# arduino_minimal.net
KiCad netlist of a schematic drawn in EAGLE
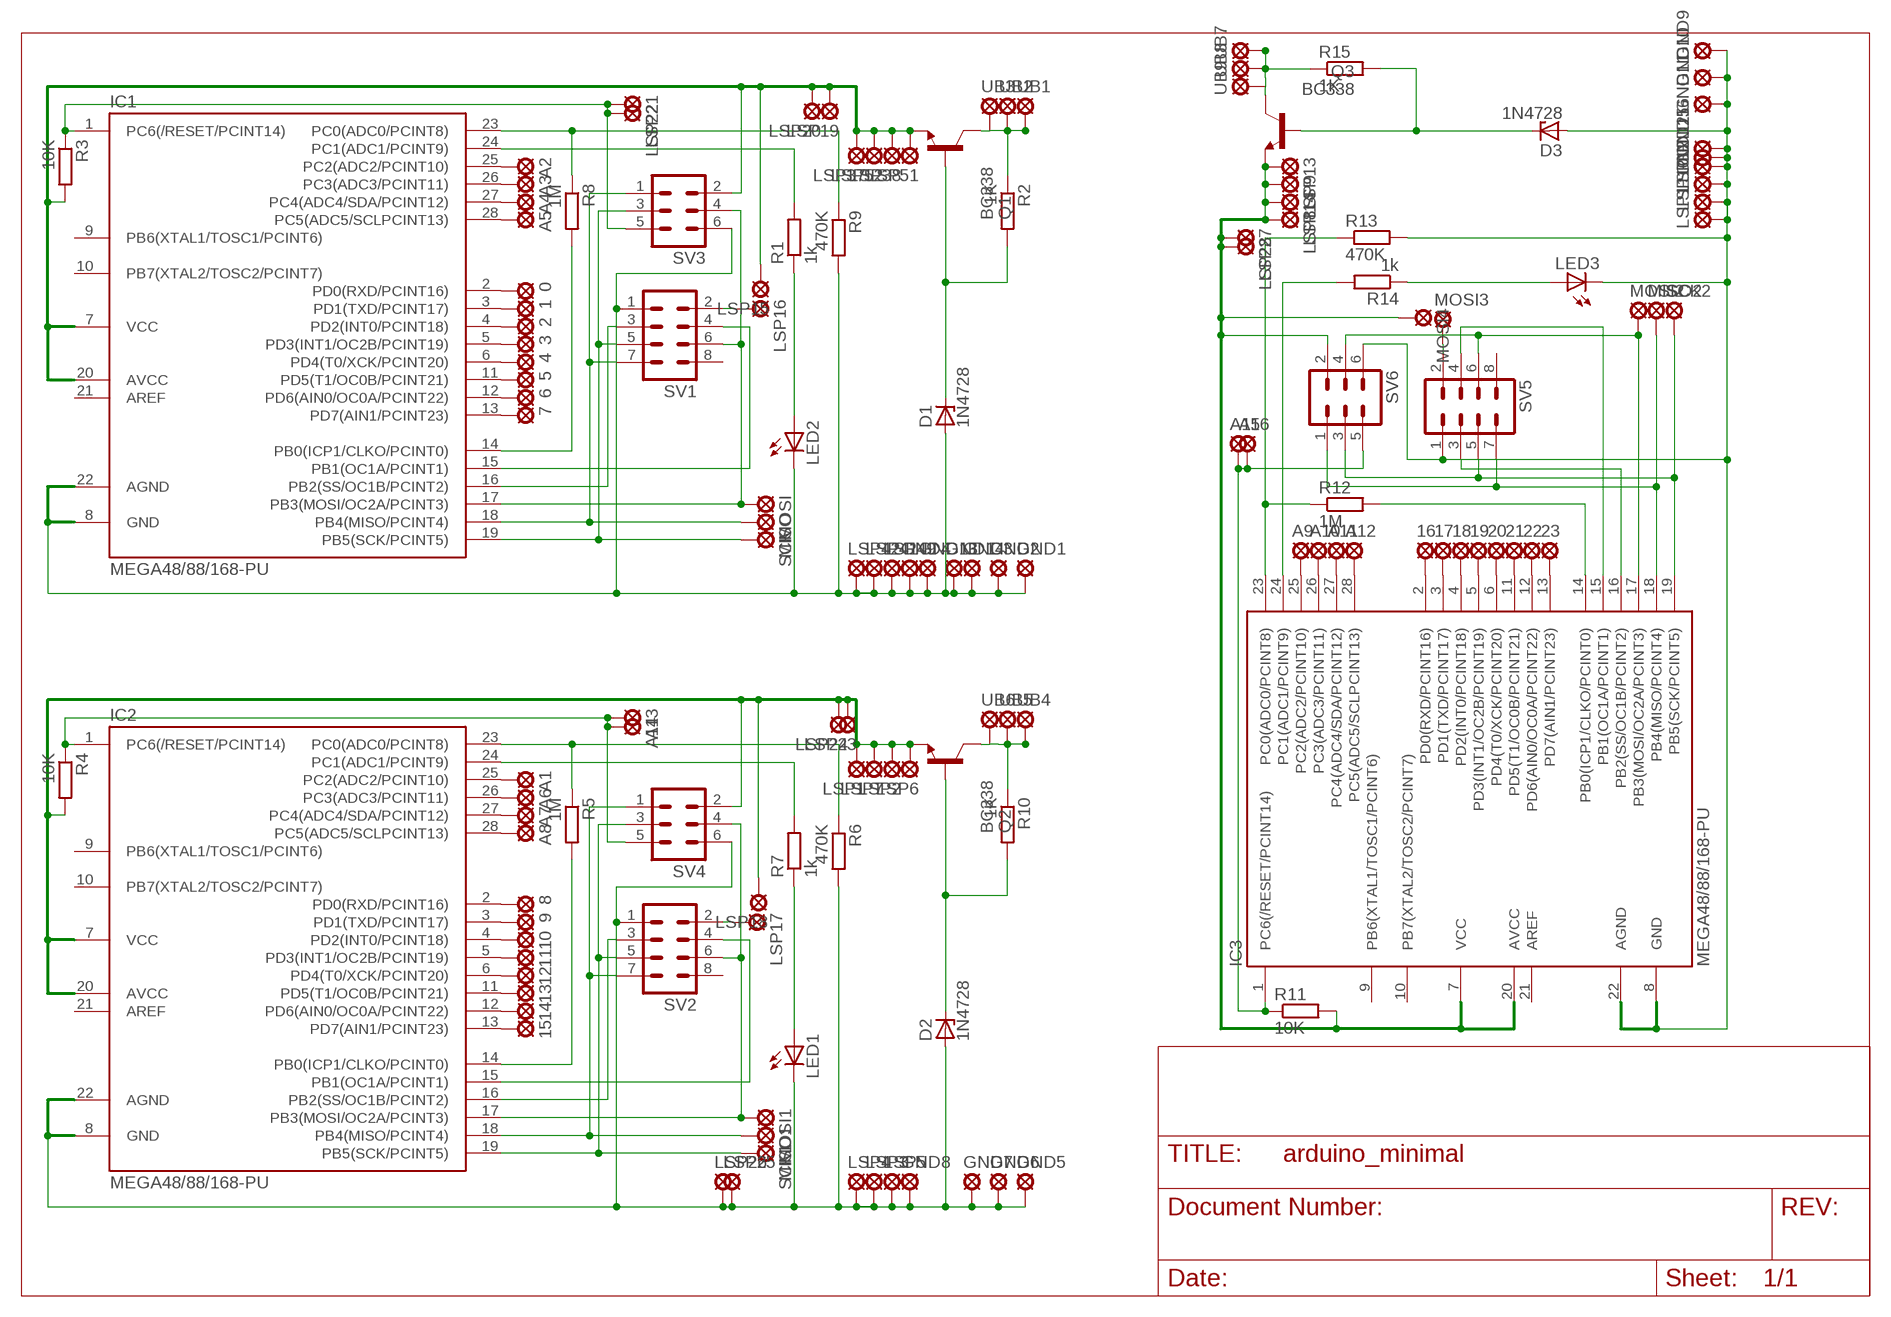
[diagram p0: schematic, sheet 1]

(export (version "E")
  (design (tool "Eeschema 10.0.6"))
  (components
    (comp (ref "0")
      (value "LSP10")
      (footprint "eagle-import:LSP10")
      (libsource (lib "eagle-import") (part "LSP10"))
    )
    (comp (ref "1")
      (value "LSP10")
      (footprint "eagle-import:LSP10")
      (libsource (lib "eagle-import") (part "LSP10"))
    )
    (comp (ref "2")
      (value "LSP10")
      (footprint "eagle-import:LSP10")
      (libsource (lib "eagle-import") (part "LSP10"))
    )
    (comp (ref "3")
      (value "LSP10")
      (footprint "eagle-import:LSP10")
      (libsource (lib "eagle-import") (part "LSP10"))
    )
    (comp (ref "4")
      (value "LSP10")
      (footprint "eagle-import:LSP10")
      (libsource (lib "eagle-import") (part "LSP10"))
    )
    (comp (ref "5")
      (value "LSP10")
      (footprint "eagle-import:LSP10")
      (libsource (lib "eagle-import") (part "LSP10"))
    )
    (comp (ref "6")
      (value "LSP10")
      (footprint "eagle-import:LSP10")
      (libsource (lib "eagle-import") (part "LSP10"))
    )
    (comp (ref "7")
      (value "LSP10")
      (footprint "eagle-import:LSP10")
      (libsource (lib "eagle-import") (part "LSP10"))
    )
    (comp (ref "8")
      (value "LSP10")
      (footprint "eagle-import:LSP10")
      (libsource (lib "eagle-import") (part "LSP10"))
    )
    (comp (ref "9")
      (value "LSP10")
      (footprint "eagle-import:LSP10")
      (libsource (lib "eagle-import") (part "LSP10"))
    )
    (comp (ref "10")
      (value "LSP10")
      (footprint "eagle-import:LSP10")
      (libsource (lib "eagle-import") (part "LSP10"))
    )
    (comp (ref "11")
      (value "LSP10")
      (footprint "eagle-import:LSP10")
      (libsource (lib "eagle-import") (part "LSP10"))
    )
    (comp (ref "12")
      (value "LSP10")
      (footprint "eagle-import:LSP10")
      (libsource (lib "eagle-import") (part "LSP10"))
    )
    (comp (ref "13")
      (value "LSP10")
      (footprint "eagle-import:LSP10")
      (libsource (lib "eagle-import") (part "LSP10"))
    )
    (comp (ref "14")
      (value "LSP10")
      (footprint "eagle-import:LSP10")
      (libsource (lib "eagle-import") (part "LSP10"))
    )
    (comp (ref "15")
      (value "LSP10")
      (footprint "eagle-import:LSP10")
      (libsource (lib "eagle-import") (part "LSP10"))
    )
    (comp (ref "16")
      (value "LSP10")
      (footprint "eagle-import:LSP10")
      (libsource (lib "eagle-import") (part "LSP10"))
    )
    (comp (ref "17")
      (value "LSP10")
      (footprint "eagle-import:LSP10")
      (libsource (lib "eagle-import") (part "LSP10"))
    )
    (comp (ref "18")
      (value "LSP10")
      (footprint "eagle-import:LSP10")
      (libsource (lib "eagle-import") (part "LSP10"))
    )
    (comp (ref "19")
      (value "LSP10")
      (footprint "eagle-import:LSP10")
      (libsource (lib "eagle-import") (part "LSP10"))
    )
    (comp (ref "20")
      (value "LSP10")
      (footprint "eagle-import:LSP10")
      (libsource (lib "eagle-import") (part "LSP10"))
    )
    (comp (ref "21")
      (value "LSP10")
      (footprint "eagle-import:LSP10")
      (libsource (lib "eagle-import") (part "LSP10"))
    )
    (comp (ref "22")
      (value "LSP10")
      (footprint "eagle-import:LSP10")
      (libsource (lib "eagle-import") (part "LSP10"))
    )
    (comp (ref "23")
      (value "LSP10")
      (footprint "eagle-import:LSP10")
      (libsource (lib "eagle-import") (part "LSP10"))
    )
    (comp (ref "A1")
      (value "LSP10")
      (footprint "eagle-import:LSP10")
      (libsource (lib "eagle-import") (part "LSP10"))
    )
    (comp (ref "A2")
      (value "LSP10")
      (footprint "eagle-import:LSP10")
      (libsource (lib "eagle-import") (part "LSP10"))
    )
    (comp (ref "A3")
      (value "LSP10")
      (footprint "eagle-import:LSP10")
      (libsource (lib "eagle-import") (part "LSP10"))
    )
    (comp (ref "A4")
      (value "LSP10")
      (footprint "eagle-import:LSP10")
      (libsource (lib "eagle-import") (part "LSP10"))
    )
    (comp (ref "A5")
      (value "LSP10")
      (footprint "eagle-import:LSP10")
      (libsource (lib "eagle-import") (part "LSP10"))
    )
    (comp (ref "A6")
      (value "LSP10")
      (footprint "eagle-import:LSP10")
      (libsource (lib "eagle-import") (part "LSP10"))
    )
    (comp (ref "A7")
      (value "LSP10")
      (footprint "eagle-import:LSP10")
      (libsource (lib "eagle-import") (part "LSP10"))
    )
    (comp (ref "A8")
      (value "LSP10")
      (footprint "eagle-import:LSP10")
      (libsource (lib "eagle-import") (part "LSP10"))
    )
    (comp (ref "A9")
      (value "LSP10")
      (footprint "eagle-import:LSP10")
      (libsource (lib "eagle-import") (part "LSP10"))
    )
    (comp (ref "A10")
      (value "LSP10")
      (footprint "eagle-import:LSP10")
      (libsource (lib "eagle-import") (part "LSP10"))
    )
    (comp (ref "A11")
      (value "LSP10")
      (footprint "eagle-import:LSP10")
      (libsource (lib "eagle-import") (part "LSP10"))
    )
    (comp (ref "A12")
      (value "LSP10")
      (footprint "eagle-import:LSP10")
      (libsource (lib "eagle-import") (part "LSP10"))
    )
    (comp (ref "A13")
      (value "LSP10")
      (footprint "eagle-import:LSP10")
      (libsource (lib "eagle-import") (part "LSP10"))
    )
    (comp (ref "A14")
      (value "LSP10")
      (footprint "eagle-import:LSP10")
      (libsource (lib "eagle-import") (part "LSP10"))
    )
    (comp (ref "A15")
      (value "LSP10")
      (footprint "eagle-import:LSP10")
      (libsource (lib "eagle-import") (part "LSP10"))
    )
    (comp (ref "A16")
      (value "LSP10")
      (footprint "eagle-import:LSP10")
      (libsource (lib "eagle-import") (part "LSP10"))
    )
    (comp (ref "D1")
      (value "1N4728")
      (footprint "eagle-import:DO41Z10")
      (libsource (lib "eagle-import") (part "1N4728"))
    )
    (comp (ref "D2")
      (value "1N4728")
      (footprint "eagle-import:DO41Z10")
      (libsource (lib "eagle-import") (part "1N4728"))
    )
    (comp (ref "D3")
      (value "1N4728")
      (footprint "eagle-import:DO41Z10")
      (libsource (lib "eagle-import") (part "1N4728"))
    )
    (comp (ref "GND1")
      (value "LSP10")
      (footprint "eagle-import:LSP10")
      (libsource (lib "eagle-import") (part "LSP10"))
    )
    (comp (ref "GND2")
      (value "LSP10")
      (footprint "eagle-import:LSP10")
      (libsource (lib "eagle-import") (part "LSP10"))
    )
    (comp (ref "GND3")
      (value "LSP10")
      (footprint "eagle-import:LSP10")
      (libsource (lib "eagle-import") (part "LSP10"))
    )
    (comp (ref "GND4")
      (value "LSP10")
      (footprint "eagle-import:LSP10")
      (libsource (lib "eagle-import") (part "LSP10"))
    )
    (comp (ref "GND5")
      (value "LSP10")
      (footprint "eagle-import:LSP10")
      (libsource (lib "eagle-import") (part "LSP10"))
    )
    (comp (ref "GND6")
      (value "LSP10")
      (footprint "eagle-import:LSP10")
      (libsource (lib "eagle-import") (part "LSP10"))
    )
    (comp (ref "GND7")
      (value "LSP10")
      (footprint "eagle-import:LSP10")
      (libsource (lib "eagle-import") (part "LSP10"))
    )
    (comp (ref "GND8")
      (value "LSP10")
      (footprint "eagle-import:LSP10")
      (libsource (lib "eagle-import") (part "LSP10"))
    )
    (comp (ref "GND9")
      (value "LSP10")
      (footprint "eagle-import:LSP10")
      (libsource (lib "eagle-import") (part "LSP10"))
    )
    (comp (ref "GND10")
      (value "LSP10")
      (footprint "eagle-import:LSP10")
      (libsource (lib "eagle-import") (part "LSP10"))
    )
    (comp (ref "GND11")
      (value "LSP10")
      (footprint "eagle-import:LSP10")
      (libsource (lib "eagle-import") (part "LSP10"))
    )
    (comp (ref "GND12")
      (value "LSP10")
      (footprint "eagle-import:LSP10")
      (libsource (lib "eagle-import") (part "LSP10"))
    )
    (comp (ref "GND13")
      (value "LSP10")
      (footprint "eagle-import:LSP10")
      (libsource (lib "eagle-import") (part "LSP10"))
    )
    (comp (ref "GND14")
      (value "LSP10")
      (footprint "eagle-import:LSP10")
      (libsource (lib "eagle-import") (part "LSP10"))
    )
    (comp (ref "GND15")
      (value "LSP10")
      (footprint "eagle-import:LSP10")
      (libsource (lib "eagle-import") (part "LSP10"))
    )
    (comp (ref "GND16")
      (value "LSP10")
      (footprint "eagle-import:LSP10")
      (libsource (lib "eagle-import") (part "LSP10"))
    )
    (comp (ref "IC1")
      (value "MEGA48/88/168-PU")
      (footprint "eagle-import:DIL28-3")
      (libsource (lib "eagle-import") (part "MEGA48/88/168-PU"))
    )
    (comp (ref "IC2")
      (value "MEGA48/88/168-PU")
      (footprint "eagle-import:DIL28-3")
      (libsource (lib "eagle-import") (part "MEGA48/88/168-PU"))
    )
    (comp (ref "IC3")
      (value "MEGA48/88/168-PU")
      (footprint "eagle-import:DIL28-3")
      (libsource (lib "eagle-import") (part "MEGA48/88/168-PU"))
    )
    (comp (ref "LED1")
      (value "LED3MM")
      (footprint "eagle-import:LED3MM")
      (libsource (lib "eagle-import") (part "LED3MM"))
    )
    (comp (ref "LED2")
      (value "LED3MM")
      (footprint "eagle-import:LED3MM")
      (libsource (lib "eagle-import") (part "LED3MM"))
    )
    (comp (ref "LED3")
      (value "LED3MM")
      (footprint "eagle-import:LED3MM")
      (libsource (lib "eagle-import") (part "LED3MM"))
    )
    (comp (ref "LSP1")
      (value "LSP10")
      (footprint "eagle-import:LSP10")
      (libsource (lib "eagle-import") (part "LSP10"))
    )
    (comp (ref "LSP2")
      (value "LSP10")
      (footprint "eagle-import:LSP10")
      (libsource (lib "eagle-import") (part "LSP10"))
    )
    (comp (ref "LSP3")
      (value "LSP10")
      (footprint "eagle-import:LSP10")
      (libsource (lib "eagle-import") (part "LSP10"))
    )
    (comp (ref "LSP4")
      (value "LSP10")
      (footprint "eagle-import:LSP10")
      (libsource (lib "eagle-import") (part "LSP10"))
    )
    (comp (ref "LSP5")
      (value "LSP10")
      (footprint "eagle-import:LSP10")
      (libsource (lib "eagle-import") (part "LSP10"))
    )
    (comp (ref "LSP6")
      (value "LSP10")
      (footprint "eagle-import:LSP10")
      (libsource (lib "eagle-import") (part "LSP10"))
    )
    (comp (ref "LSP7")
      (value "LSP10")
      (footprint "eagle-import:LSP10")
      (libsource (lib "eagle-import") (part "LSP10"))
    )
    (comp (ref "LSP8")
      (value "LSP10")
      (footprint "eagle-import:LSP10")
      (libsource (lib "eagle-import") (part "LSP10"))
    )
    (comp (ref "LSP9")
      (value "LSP10")
      (footprint "eagle-import:LSP10")
      (libsource (lib "eagle-import") (part "LSP10"))
    )
    (comp (ref "LSP10")
      (value "LSP10")
      (footprint "eagle-import:LSP10")
      (libsource (lib "eagle-import") (part "LSP10"))
    )
    (comp (ref "LSP11")
      (value "LSP10")
      (footprint "eagle-import:LSP10")
      (libsource (lib "eagle-import") (part "LSP10"))
    )
    (comp (ref "LSP12")
      (value "LSP10")
      (footprint "eagle-import:LSP10")
      (libsource (lib "eagle-import") (part "LSP10"))
    )
    (comp (ref "LSP13")
      (value "LSP10")
      (footprint "eagle-import:LSP10")
      (libsource (lib "eagle-import") (part "LSP10"))
    )
    (comp (ref "LSP14")
      (value "LSP10")
      (footprint "eagle-import:LSP10")
      (libsource (lib "eagle-import") (part "LSP10"))
    )
    (comp (ref "LSP15")
      (value "LSP10")
      (footprint "eagle-import:LSP10")
      (libsource (lib "eagle-import") (part "LSP10"))
    )
    (comp (ref "LSP16")
      (value "LSP10")
      (footprint "eagle-import:LSP10")
      (libsource (lib "eagle-import") (part "LSP10"))
    )
    (comp (ref "LSP17")
      (value "LSP10")
      (footprint "eagle-import:LSP10")
      (libsource (lib "eagle-import") (part "LSP10"))
    )
    (comp (ref "LSP18")
      (value "LSP10")
      (footprint "eagle-import:LSP10")
      (libsource (lib "eagle-import") (part "LSP10"))
    )
    (comp (ref "LSP19")
      (value "LSP10")
      (footprint "eagle-import:LSP10")
      (libsource (lib "eagle-import") (part "LSP10"))
    )
    (comp (ref "LSP20")
      (value "LSP10")
      (footprint "eagle-import:LSP10")
      (libsource (lib "eagle-import") (part "LSP10"))
    )
    (comp (ref "LSP21")
      (value "LSP10")
      (footprint "eagle-import:LSP10")
      (libsource (lib "eagle-import") (part "LSP10"))
    )
    (comp (ref "LSP22")
      (value "LSP10")
      (footprint "eagle-import:LSP10")
      (libsource (lib "eagle-import") (part "LSP10"))
    )
    (comp (ref "LSP23")
      (value "LSP10")
      (footprint "eagle-import:LSP10")
      (libsource (lib "eagle-import") (part "LSP10"))
    )
    (comp (ref "LSP24")
      (value "LSP10")
      (footprint "eagle-import:LSP10")
      (libsource (lib "eagle-import") (part "LSP10"))
    )
    (comp (ref "LSP25")
      (value "LSP10")
      (footprint "eagle-import:LSP10")
      (libsource (lib "eagle-import") (part "LSP10"))
    )
    (comp (ref "LSP26")
      (value "LSP10")
      (footprint "eagle-import:LSP10")
      (libsource (lib "eagle-import") (part "LSP10"))
    )
    (comp (ref "LSP27")
      (value "LSP10")
      (footprint "eagle-import:LSP10")
      (libsource (lib "eagle-import") (part "LSP10"))
    )
    (comp (ref "LSP28")
      (value "LSP10")
      (footprint "eagle-import:LSP10")
      (libsource (lib "eagle-import") (part "LSP10"))
    )
    (comp (ref "LSP37")
      (value "LSP10")
      (footprint "eagle-import:LSP10")
      (libsource (lib "eagle-import") (part "LSP10"))
    )
    (comp (ref "LSP38")
      (value "LSP10")
      (footprint "eagle-import:LSP10")
      (libsource (lib "eagle-import") (part "LSP10"))
    )
    (comp (ref "LSP41")
      (value "LSP10")
      (footprint "eagle-import:LSP10")
      (libsource (lib "eagle-import") (part "LSP10"))
    )
    (comp (ref "LSP42")
      (value "LSP10")
      (footprint "eagle-import:LSP10")
      (libsource (lib "eagle-import") (part "LSP10"))
    )
    (comp (ref "LSP49")
      (value "LSP10")
      (footprint "eagle-import:LSP10")
      (libsource (lib "eagle-import") (part "LSP10"))
    )
    (comp (ref "LSP51")
      (value "LSP10")
      (footprint "eagle-import:LSP10")
      (libsource (lib "eagle-import") (part "LSP10"))
    )
    (comp (ref "LSP52")
      (value "LSP10")
      (footprint "eagle-import:LSP10")
      (libsource (lib "eagle-import") (part "LSP10"))
    )
    (comp (ref "MISO")
      (value "LSP10")
      (footprint "eagle-import:LSP10")
      (libsource (lib "eagle-import") (part "LSP10"))
    )
    (comp (ref "MISO1")
      (value "LSP10")
      (footprint "eagle-import:LSP10")
      (libsource (lib "eagle-import") (part "LSP10"))
    )
    (comp (ref "MISO2")
      (value "LSP10")
      (footprint "eagle-import:LSP10")
      (libsource (lib "eagle-import") (part "LSP10"))
    )
    (comp (ref "MOSI")
      (value "LSP10")
      (footprint "eagle-import:LSP10")
      (libsource (lib "eagle-import") (part "LSP10"))
    )
    (comp (ref "MOSI1")
      (value "LSP10")
      (footprint "eagle-import:LSP10")
      (libsource (lib "eagle-import") (part "LSP10"))
    )
    (comp (ref "MOSI2")
      (value "LSP10")
      (footprint "eagle-import:LSP10")
      (libsource (lib "eagle-import") (part "LSP10"))
    )
    (comp (ref "MOSI3")
      (value "LSP10")
      (footprint "eagle-import:LSP10")
      (libsource (lib "eagle-import") (part "LSP10"))
    )
    (comp (ref "MOSI4")
      (value "LSP10")
      (footprint "eagle-import:LSP10")
      (libsource (lib "eagle-import") (part "LSP10"))
    )
    (comp (ref "Q1")
      (value "BC338")
      (footprint "eagle-import:TO92-EBC")
      (libsource (lib "eagle-import") (part "BC338"))
    )
    (comp (ref "Q2")
      (value "BC338")
      (footprint "eagle-import:TO92-EBC")
      (libsource (lib "eagle-import") (part "BC338"))
    )
    (comp (ref "Q3")
      (value "BC338")
      (footprint "eagle-import:TO92-EBC")
      (libsource (lib "eagle-import") (part "BC338"))
    )
    (comp (ref "R1")
      (value "1k")
      (footprint "eagle-import:0204_7")
      (libsource (lib "eagle-import") (part "R-EU_0204/7"))
    )
    (comp (ref "R2")
      (value "1K")
      (footprint "eagle-import:0204_7")
      (libsource (lib "eagle-import") (part "R-EU_0204/7"))
    )
    (comp (ref "R3")
      (value "10K")
      (footprint "eagle-import:0204_7")
      (libsource (lib "eagle-import") (part "R-EU_0204/7"))
    )
    (comp (ref "R4")
      (value "10K")
      (footprint "eagle-import:0204_7")
      (libsource (lib "eagle-import") (part "R-EU_0204/7"))
    )
    (comp (ref "R5")
      (value "1M")
      (footprint "eagle-import:0204_7")
      (libsource (lib "eagle-import") (part "R-EU_0204/7"))
    )
    (comp (ref "R6")
      (value "470K")
      (footprint "eagle-import:0204_7")
      (libsource (lib "eagle-import") (part "R-EU_0204/7"))
    )
    (comp (ref "R7")
      (value "1k")
      (footprint "eagle-import:0204_7")
      (libsource (lib "eagle-import") (part "R-EU_0204/7"))
    )
    (comp (ref "R8")
      (value "1M")
      (footprint "eagle-import:0204_7")
      (libsource (lib "eagle-import") (part "R-EU_0204/7"))
    )
    (comp (ref "R9")
      (value "470K")
      (footprint "eagle-import:0204_7")
      (libsource (lib "eagle-import") (part "R-EU_0204/7"))
    )
    (comp (ref "R10")
      (value "1K")
      (footprint "eagle-import:0204_7")
      (libsource (lib "eagle-import") (part "R-EU_0204/7"))
    )
    (comp (ref "R11")
      (value "10K")
      (footprint "eagle-import:0204_7")
      (libsource (lib "eagle-import") (part "R-EU_0204/7"))
    )
    (comp (ref "R12")
      (value "1M")
      (footprint "eagle-import:0204_7")
      (libsource (lib "eagle-import") (part "R-EU_0204/7"))
    )
    (comp (ref "R13")
      (value "470K")
      (footprint "eagle-import:0204_7")
      (libsource (lib "eagle-import") (part "R-EU_0204/7"))
    )
    (comp (ref "R14")
      (value "1k")
      (footprint "eagle-import:0204_7")
      (libsource (lib "eagle-import") (part "R-EU_0204/7"))
    )
    (comp (ref "R15")
      (value "1K")
      (footprint "eagle-import:0204_7")
      (libsource (lib "eagle-import") (part "R-EU_0204/7"))
    )
    (comp (ref "SCK")
      (value "LSP10")
      (footprint "eagle-import:LSP10")
      (libsource (lib "eagle-import") (part "LSP10"))
    )
    (comp (ref "SCK1")
      (value "LSP10")
      (footprint "eagle-import:LSP10")
      (libsource (lib "eagle-import") (part "LSP10"))
    )
    (comp (ref "SCK2")
      (value "LSP10")
      (footprint "eagle-import:LSP10")
      (libsource (lib "eagle-import") (part "LSP10"))
    )
    (comp (ref "SV1")
      (value "MA04-2")
      (footprint "eagle-import:MA04-2")
      (libsource (lib "eagle-import") (part "MA04-2"))
    )
    (comp (ref "SV2")
      (value "MA04-2")
      (footprint "eagle-import:MA04-2")
      (libsource (lib "eagle-import") (part "MA04-2"))
    )
    (comp (ref "SV3")
      (value "MA03-2")
      (footprint "eagle-import:MA03-2")
      (libsource (lib "eagle-import") (part "MA03-2"))
    )
    (comp (ref "SV4")
      (value "MA03-2")
      (footprint "eagle-import:MA03-2")
      (libsource (lib "eagle-import") (part "MA03-2"))
    )
    (comp (ref "SV5")
      (value "MA04-2")
      (footprint "eagle-import:MA04-2")
      (libsource (lib "eagle-import") (part "MA04-2"))
    )
    (comp (ref "SV6")
      (value "MA03-2")
      (footprint "eagle-import:MA03-2")
      (libsource (lib "eagle-import") (part "MA03-2"))
    )
    (comp (ref "UB1")
      (value "LSP10")
      (footprint "eagle-import:LSP10")
      (libsource (lib "eagle-import") (part "LSP10"))
    )
    (comp (ref "UB2")
      (value "LSP10")
      (footprint "eagle-import:LSP10")
      (libsource (lib "eagle-import") (part "LSP10"))
    )
    (comp (ref "UB3")
      (value "LSP10")
      (footprint "eagle-import:LSP10")
      (libsource (lib "eagle-import") (part "LSP10"))
    )
    (comp (ref "UB4")
      (value "LSP10")
      (footprint "eagle-import:LSP10")
      (libsource (lib "eagle-import") (part "LSP10"))
    )
    (comp (ref "UB5")
      (value "LSP10")
      (footprint "eagle-import:LSP10")
      (libsource (lib "eagle-import") (part "LSP10"))
    )
    (comp (ref "UB6")
      (value "LSP10")
      (footprint "eagle-import:LSP10")
      (libsource (lib "eagle-import") (part "LSP10"))
    )
    (comp (ref "UB7")
      (value "LSP10")
      (footprint "eagle-import:LSP10")
      (libsource (lib "eagle-import") (part "LSP10"))
    )
    (comp (ref "UB8")
      (value "LSP10")
      (footprint "eagle-import:LSP10")
      (libsource (lib "eagle-import") (part "LSP10"))
    )
    (comp (ref "UB9")
      (value "LSP10")
      (footprint "eagle-import:LSP10")
      (libsource (lib "eagle-import") (part "LSP10"))
    )
  )
  (nets
    (net (code "1") (name "Net-(D1-PadC)") (class "Default")
      (node (ref "D1") (pin "C") (pinfunction "C_C") (pintype "passive"))
      (node (ref "Q1") (pin "B") (pinfunction "B_B") (pintype "passive"))
      (node (ref "R2") (pin "2") (pinfunction "2_2") (pintype "passive"))
    )
    (net (code "2") (name "Net-(D2-PadC)") (class "Default")
      (node (ref "D2") (pin "C") (pinfunction "C_C") (pintype "passive"))
      (node (ref "Q2") (pin "B") (pinfunction "B_B") (pintype "passive"))
      (node (ref "R10") (pin "2") (pinfunction "2_2") (pintype "passive"))
    )
    (net (code "3") (name "Net-(D3-PadC)") (class "Default")
      (node (ref "D3") (pin "C") (pinfunction "C_C") (pintype "passive"))
      (node (ref "Q3") (pin "B") (pinfunction "B_B") (pintype "passive"))
      (node (ref "R15") (pin "2") (pinfunction "2_2") (pintype "passive"))
    )
    (net (code "4") (name "Net-(IC1-AGND)") (class "Default")
      (node (ref "D1") (pin "A") (pinfunction "A_A") (pintype "passive"))
      (node (ref "GND1") (pin "MP") (pinfunction "MP_MP") (pintype "passive"))
      (node (ref "GND13") (pin "MP") (pinfunction "MP_MP") (pintype "passive"))
      (node (ref "GND14") (pin "MP") (pinfunction "MP_MP") (pintype "passive"))
      (node (ref "GND2") (pin "MP") (pinfunction "MP_MP") (pintype "passive"))
      (node (ref "GND3") (pin "MP") (pinfunction "MP_MP") (pintype "passive"))
      (node (ref "GND4") (pin "MP") (pinfunction "MP_MP") (pintype "passive"))
      (node (ref "IC1") (pin "22") (pinfunction "AGND_22") (pintype "power_in"))
      (node (ref "IC1") (pin "8") (pinfunction "GND_8") (pintype "power_in"))
      (node (ref "LED2") (pin "K") (pinfunction "C_K") (pintype "passive"))
      (node (ref "LSP41") (pin "MP") (pinfunction "MP_MP") (pintype "passive"))
      (node (ref "LSP42") (pin "MP") (pinfunction "MP_MP") (pintype "passive"))
      (node (ref "LSP49") (pin "MP") (pinfunction "MP_MP") (pintype "passive"))
      (node (ref "R9") (pin "2") (pinfunction "2_2") (pintype "passive"))
      (node (ref "SV1") (pin "1") (pinfunction "1_1") (pintype "passive"))
      (node (ref "SV3") (pin "6") (pinfunction "6_6") (pintype "passive"))
    )
    (net (code "5") (name "Net-(IC1-AVCC)") (class "Default")
      (node (ref "IC1") (pin "20") (pinfunction "AVCC_20") (pintype "passive"))
      (node (ref "IC1") (pin "7") (pinfunction "VCC_7") (pintype "power_in"))
      (node (ref "LSP15") (pin "MP") (pinfunction "MP_MP") (pintype "passive"))
      (node (ref "LSP19") (pin "MP") (pinfunction "MP_MP") (pintype "passive"))
      (node (ref "LSP20") (pin "MP") (pinfunction "MP_MP") (pintype "passive"))
      (node (ref "LSP37") (pin "MP") (pinfunction "MP_MP") (pintype "passive"))
      (node (ref "LSP38") (pin "MP") (pinfunction "MP_MP") (pintype "passive"))
      (node (ref "LSP51") (pin "MP") (pinfunction "MP_MP") (pintype "passive"))
      (node (ref "LSP52") (pin "MP") (pinfunction "MP_MP") (pintype "passive"))
      (node (ref "Q1") (pin "E") (pinfunction "E_E") (pintype "passive"))
      (node (ref "R3") (pin "2") (pinfunction "2_2") (pintype "passive"))
      (node (ref "SV3") (pin "2") (pinfunction "2_2") (pintype "passive"))
    )
    (net (code "6") (name "Net-(IC1-PB0(ICP1{slash}CLKO{slash}PCINT0))") (class "Default")
      (node (ref "IC1") (pin "14") (pinfunction "PB0(ICP1/CLKO/PCINT0)_14") (pintype "bidirectional"))
      (node (ref "R8") (pin "2") (pinfunction "2_2") (pintype "passive"))
    )
    (net (code "7") (name "Net-(IC1-PB1(OC1A{slash}PCINT1))") (class "Default")
      (node (ref "IC1") (pin "15") (pinfunction "PB1(OC1A/PCINT1)_15") (pintype "bidirectional"))
      (node (ref "SV1") (pin "4") (pinfunction "4_4") (pintype "passive"))
    )
    (net (code "8") (name "Net-(IC1-PB2(SS{slash}OC1B{slash}PCINT2))") (class "Default")
      (node (ref "IC1") (pin "16") (pinfunction "PB2(SS/OC1B/PCINT2)_16") (pintype "bidirectional"))
      (node (ref "SV1") (pin "3") (pinfunction "3_3") (pintype "passive"))
    )
    (net (code "9") (name "Net-(IC1-PB3(MOSI{slash}OC2A{slash}PCINT3))") (class "Default")
      (node (ref "IC1") (pin "17") (pinfunction "PB3(MOSI/OC2A/PCINT3)_17") (pintype "bidirectional"))
      (node (ref "MOSI") (pin "MP") (pinfunction "MP_MP") (pintype "passive"))
      (node (ref "SV1") (pin "6") (pinfunction "6_6") (pintype "passive"))
      (node (ref "SV3") (pin "4") (pinfunction "4_4") (pintype "passive"))
    )
    (net (code "10") (name "Net-(IC1-PB4(MISO{slash}PCINT4))") (class "Default")
      (node (ref "IC1") (pin "18") (pinfunction "PB4(MISO/PCINT4)_18") (pintype "bidirectional"))
      (node (ref "MISO") (pin "MP") (pinfunction "MP_MP") (pintype "passive"))
      (node (ref "SV1") (pin "7") (pinfunction "7_7") (pintype "passive"))
      (node (ref "SV3") (pin "1") (pinfunction "1_1") (pintype "passive"))
    )
    (net (code "11") (name "Net-(IC1-PB5(SCK{slash}PCINT5))") (class "Default")
      (node (ref "IC1") (pin "19") (pinfunction "PB5(SCK/PCINT5)_19") (pintype "bidirectional"))
      (node (ref "SCK") (pin "MP") (pinfunction "MP_MP") (pintype "passive"))
      (node (ref "SV1") (pin "5") (pinfunction "5_5") (pintype "passive"))
      (node (ref "SV3") (pin "3") (pinfunction "3_3") (pintype "passive"))
    )
    (net (code "12") (name "Net-(IC1-PC0(ADC0{slash}PCINT8))") (class "Default")
      (node (ref "IC1") (pin "23") (pinfunction "PC0(ADC0/PCINT8)_23") (pintype "bidirectional"))
      (node (ref "R8") (pin "1") (pinfunction "1_1") (pintype "passive"))
      (node (ref "R9") (pin "1") (pinfunction "1_1") (pintype "passive"))
    )
    (net (code "13") (name "Net-(IC1-PC1(ADC1{slash}PCINT9))") (class "Default")
      (node (ref "IC1") (pin "24") (pinfunction "PC1(ADC1/PCINT9)_24") (pintype "bidirectional"))
      (node (ref "R1") (pin "2") (pinfunction "2_2") (pintype "passive"))
    )
    (net (code "14") (name "Net-(IC1-PC2(ADC2{slash}PCINT10))") (class "Default")
      (node (ref "A2") (pin "MP") (pinfunction "MP_MP") (pintype "passive"))
      (node (ref "IC1") (pin "25") (pinfunction "PC2(ADC2/PCINT10)_25") (pintype "bidirectional"))
    )
    (net (code "15") (name "Net-(IC1-PC3(ADC3{slash}PCINT11))") (class "Default")
      (node (ref "A3") (pin "MP") (pinfunction "MP_MP") (pintype "passive"))
      (node (ref "IC1") (pin "26") (pinfunction "PC3(ADC3/PCINT11)_26") (pintype "bidirectional"))
    )
    (net (code "16") (name "Net-(IC1-PC4(ADC4{slash}SDA{slash}PCINT12))") (class "Default")
      (node (ref "A4") (pin "MP") (pinfunction "MP_MP") (pintype "passive"))
      (node (ref "IC1") (pin "27") (pinfunction "PC4(ADC4/SDA/PCINT12)_27") (pintype "bidirectional"))
    )
    (net (code "17") (name "Net-(IC1-PC5(ADC5{slash}SCLPCINT13))") (class "Default")
      (node (ref "A5") (pin "MP") (pinfunction "MP_MP") (pintype "passive"))
      (node (ref "IC1") (pin "28") (pinfunction "PC5(ADC5/SCLPCINT13)_28") (pintype "bidirectional"))
    )
    (net (code "18") (name "Net-(IC1-PC6({slash}RESET{slash}PCINT14))") (class "Default")
      (node (ref "IC1") (pin "1") (pinfunction "PC6(/RESET/PCINT14)_1") (pintype "bidirectional"))
      (node (ref "LSP21") (pin "MP") (pinfunction "MP_MP") (pintype "passive"))
      (node (ref "LSP22") (pin "MP") (pinfunction "MP_MP") (pintype "passive"))
      (node (ref "R3") (pin "1") (pinfunction "1_1") (pintype "passive"))
      (node (ref "SV3") (pin "5") (pinfunction "5_5") (pintype "passive"))
    )
    (net (code "19") (name "Net-(IC1-PD0(RXD{slash}PCINT16))") (class "Default")
      (node (ref "0") (pin "MP") (pinfunction "MP_MP") (pintype "passive"))
      (node (ref "IC1") (pin "2") (pinfunction "PD0(RXD/PCINT16)_2") (pintype "bidirectional"))
    )
    (net (code "20") (name "Net-(IC1-PD1(TXD{slash}PCINT17))") (class "Default")
      (node (ref "1") (pin "MP") (pinfunction "MP_MP") (pintype "passive"))
      (node (ref "IC1") (pin "3") (pinfunction "PD1(TXD/PCINT17)_3") (pintype "bidirectional"))
    )
    (net (code "21") (name "Net-(IC1-PD2(INT0{slash}PCINT18))") (class "Default")
      (node (ref "2") (pin "MP") (pinfunction "MP_MP") (pintype "passive"))
      (node (ref "IC1") (pin "4") (pinfunction "PD2(INT0/PCINT18)_4") (pintype "bidirectional"))
    )
    (net (code "22") (name "Net-(IC1-PD3(INT1{slash}OC2B{slash}PCINT19))") (class "Default")
      (node (ref "3") (pin "MP") (pinfunction "MP_MP") (pintype "passive"))
      (node (ref "IC1") (pin "5") (pinfunction "PD3(INT1/OC2B/PCINT19)_5") (pintype "bidirectional"))
    )
    (net (code "23") (name "Net-(IC1-PD4(T0{slash}XCK{slash}PCINT20))") (class "Default")
      (node (ref "4") (pin "MP") (pinfunction "MP_MP") (pintype "passive"))
      (node (ref "IC1") (pin "6") (pinfunction "PD4(T0/XCK/PCINT20)_6") (pintype "bidirectional"))
    )
    (net (code "24") (name "Net-(IC1-PD5(T1{slash}OC0B{slash}PCINT21))") (class "Default")
      (node (ref "5") (pin "MP") (pinfunction "MP_MP") (pintype "passive"))
      (node (ref "IC1") (pin "11") (pinfunction "PD5(T1/OC0B/PCINT21)_11") (pintype "bidirectional"))
    )
    (net (code "25") (name "Net-(IC1-PD6(AIN0{slash}OC0A{slash}PCINT22))") (class "Default")
      (node (ref "6") (pin "MP") (pinfunction "MP_MP") (pintype "passive"))
      (node (ref "IC1") (pin "12") (pinfunction "PD6(AIN0/OC0A/PCINT22)_12") (pintype "bidirectional"))
    )
    (net (code "26") (name "Net-(IC1-PD7(AIN1{slash}PCINT23))") (class "Default")
      (node (ref "7") (pin "MP") (pinfunction "MP_MP") (pintype "passive"))
      (node (ref "IC1") (pin "13") (pinfunction "PD7(AIN1/PCINT23)_13") (pintype "bidirectional"))
    )
    (net (code "27") (name "Net-(IC2-AGND)") (class "Default")
      (node (ref "D2") (pin "A") (pinfunction "A_A") (pintype "passive"))
      (node (ref "GND5") (pin "MP") (pinfunction "MP_MP") (pintype "passive"))
      (node (ref "GND6") (pin "MP") (pinfunction "MP_MP") (pintype "passive"))
      (node (ref "GND7") (pin "MP") (pinfunction "MP_MP") (pintype "passive"))
      (node (ref "GND8") (pin "MP") (pinfunction "MP_MP") (pintype "passive"))
      (node (ref "IC2") (pin "22") (pinfunction "AGND_22") (pintype "power_in"))
      (node (ref "IC2") (pin "8") (pinfunction "GND_8") (pintype "power_in"))
      (node (ref "LED1") (pin "K") (pinfunction "C_K") (pintype "passive"))
      (node (ref "LSP25") (pin "MP") (pinfunction "MP_MP") (pintype "passive"))
      (node (ref "LSP26") (pin "MP") (pinfunction "MP_MP") (pintype "passive"))
      (node (ref "LSP3") (pin "MP") (pinfunction "MP_MP") (pintype "passive"))
      (node (ref "LSP4") (pin "MP") (pinfunction "MP_MP") (pintype "passive"))
      (node (ref "LSP5") (pin "MP") (pinfunction "MP_MP") (pintype "passive"))
      (node (ref "R6") (pin "2") (pinfunction "2_2") (pintype "passive"))
      (node (ref "SV2") (pin "1") (pinfunction "1_1") (pintype "passive"))
      (node (ref "SV4") (pin "6") (pinfunction "6_6") (pintype "passive"))
    )
    (net (code "28") (name "Net-(IC2-AVCC)") (class "Default")
      (node (ref "IC2") (pin "20") (pinfunction "AVCC_20") (pintype "passive"))
      (node (ref "IC2") (pin "7") (pinfunction "VCC_7") (pintype "power_in"))
      (node (ref "LSP1") (pin "MP") (pinfunction "MP_MP") (pintype "passive"))
      (node (ref "LSP18") (pin "MP") (pinfunction "MP_MP") (pintype "passive"))
      (node (ref "LSP2") (pin "MP") (pinfunction "MP_MP") (pintype "passive"))
      (node (ref "LSP23") (pin "MP") (pinfunction "MP_MP") (pintype "passive"))
      (node (ref "LSP24") (pin "MP") (pinfunction "MP_MP") (pintype "passive"))
      (node (ref "LSP6") (pin "MP") (pinfunction "MP_MP") (pintype "passive"))
      (node (ref "LSP7") (pin "MP") (pinfunction "MP_MP") (pintype "passive"))
      (node (ref "Q2") (pin "E") (pinfunction "E_E") (pintype "passive"))
      (node (ref "R4") (pin "2") (pinfunction "2_2") (pintype "passive"))
      (node (ref "SV4") (pin "2") (pinfunction "2_2") (pintype "passive"))
    )
    (net (code "29") (name "Net-(IC2-PB0(ICP1{slash}CLKO{slash}PCINT0))") (class "Default")
      (node (ref "IC2") (pin "14") (pinfunction "PB0(ICP1/CLKO/PCINT0)_14") (pintype "bidirectional"))
      (node (ref "R5") (pin "2") (pinfunction "2_2") (pintype "passive"))
    )
    (net (code "30") (name "Net-(IC2-PB1(OC1A{slash}PCINT1))") (class "Default")
      (node (ref "IC2") (pin "15") (pinfunction "PB1(OC1A/PCINT1)_15") (pintype "bidirectional"))
      (node (ref "SV2") (pin "4") (pinfunction "4_4") (pintype "passive"))
    )
    (net (code "31") (name "Net-(IC2-PB2(SS{slash}OC1B{slash}PCINT2))") (class "Default")
      (node (ref "IC2") (pin "16") (pinfunction "PB2(SS/OC1B/PCINT2)_16") (pintype "bidirectional"))
      (node (ref "SV2") (pin "3") (pinfunction "3_3") (pintype "passive"))
    )
    (net (code "32") (name "Net-(IC2-PB3(MOSI{slash}OC2A{slash}PCINT3))") (class "Default")
      (node (ref "IC2") (pin "17") (pinfunction "PB3(MOSI/OC2A/PCINT3)_17") (pintype "bidirectional"))
      (node (ref "MOSI1") (pin "MP") (pinfunction "MP_MP") (pintype "passive"))
      (node (ref "SV2") (pin "6") (pinfunction "6_6") (pintype "passive"))
      (node (ref "SV4") (pin "4") (pinfunction "4_4") (pintype "passive"))
    )
    (net (code "33") (name "Net-(IC2-PB4(MISO{slash}PCINT4))") (class "Default")
      (node (ref "IC2") (pin "18") (pinfunction "PB4(MISO/PCINT4)_18") (pintype "bidirectional"))
      (node (ref "MISO1") (pin "MP") (pinfunction "MP_MP") (pintype "passive"))
      (node (ref "SV2") (pin "7") (pinfunction "7_7") (pintype "passive"))
      (node (ref "SV4") (pin "1") (pinfunction "1_1") (pintype "passive"))
    )
    (net (code "34") (name "Net-(IC2-PB5(SCK{slash}PCINT5))") (class "Default")
      (node (ref "IC2") (pin "19") (pinfunction "PB5(SCK/PCINT5)_19") (pintype "bidirectional"))
      (node (ref "SCK1") (pin "MP") (pinfunction "MP_MP") (pintype "passive"))
      (node (ref "SV2") (pin "5") (pinfunction "5_5") (pintype "passive"))
      (node (ref "SV4") (pin "3") (pinfunction "3_3") (pintype "passive"))
    )
    (net (code "35") (name "Net-(IC2-PC0(ADC0{slash}PCINT8))") (class "Default")
      (node (ref "IC2") (pin "23") (pinfunction "PC0(ADC0/PCINT8)_23") (pintype "bidirectional"))
      (node (ref "R5") (pin "1") (pinfunction "1_1") (pintype "passive"))
      (node (ref "R6") (pin "1") (pinfunction "1_1") (pintype "passive"))
    )
    (net (code "36") (name "Net-(IC2-PC1(ADC1{slash}PCINT9))") (class "Default")
      (node (ref "IC2") (pin "24") (pinfunction "PC1(ADC1/PCINT9)_24") (pintype "bidirectional"))
      (node (ref "R7") (pin "2") (pinfunction "2_2") (pintype "passive"))
    )
    (net (code "37") (name "Net-(IC2-PC2(ADC2{slash}PCINT10))") (class "Default")
      (node (ref "A1") (pin "MP") (pinfunction "MP_MP") (pintype "passive"))
      (node (ref "IC2") (pin "25") (pinfunction "PC2(ADC2/PCINT10)_25") (pintype "bidirectional"))
    )
    (net (code "38") (name "Net-(IC2-PC3(ADC3{slash}PCINT11))") (class "Default")
      (node (ref "A6") (pin "MP") (pinfunction "MP_MP") (pintype "passive"))
      (node (ref "IC2") (pin "26") (pinfunction "PC3(ADC3/PCINT11)_26") (pintype "bidirectional"))
    )
    (net (code "39") (name "Net-(IC2-PC4(ADC4{slash}SDA{slash}PCINT12))") (class "Default")
      (node (ref "A7") (pin "MP") (pinfunction "MP_MP") (pintype "passive"))
      (node (ref "IC2") (pin "27") (pinfunction "PC4(ADC4/SDA/PCINT12)_27") (pintype "bidirectional"))
    )
    (net (code "40") (name "Net-(IC2-PC5(ADC5{slash}SCLPCINT13))") (class "Default")
      (node (ref "A8") (pin "MP") (pinfunction "MP_MP") (pintype "passive"))
      (node (ref "IC2") (pin "28") (pinfunction "PC5(ADC5/SCLPCINT13)_28") (pintype "bidirectional"))
    )
    (net (code "41") (name "Net-(IC2-PC6({slash}RESET{slash}PCINT14))") (class "Default")
      (node (ref "A13") (pin "MP") (pinfunction "MP_MP") (pintype "passive"))
      (node (ref "A14") (pin "MP") (pinfunction "MP_MP") (pintype "passive"))
      (node (ref "IC2") (pin "1") (pinfunction "PC6(/RESET/PCINT14)_1") (pintype "bidirectional"))
      (node (ref "R4") (pin "1") (pinfunction "1_1") (pintype "passive"))
      (node (ref "SV4") (pin "5") (pinfunction "5_5") (pintype "passive"))
    )
    (net (code "42") (name "Net-(IC2-PD0(RXD{slash}PCINT16))") (class "Default")
      (node (ref "8") (pin "MP") (pinfunction "MP_MP") (pintype "passive"))
      (node (ref "IC2") (pin "2") (pinfunction "PD0(RXD/PCINT16)_2") (pintype "bidirectional"))
    )
    (net (code "43") (name "Net-(IC2-PD1(TXD{slash}PCINT17))") (class "Default")
      (node (ref "9") (pin "MP") (pinfunction "MP_MP") (pintype "passive"))
      (node (ref "IC2") (pin "3") (pinfunction "PD1(TXD/PCINT17)_3") (pintype "bidirectional"))
    )
    (net (code "44") (name "Net-(IC2-PD2(INT0{slash}PCINT18))") (class "Default")
      (node (ref "10") (pin "MP") (pinfunction "MP_MP") (pintype "passive"))
      (node (ref "IC2") (pin "4") (pinfunction "PD2(INT0/PCINT18)_4") (pintype "bidirectional"))
    )
    (net (code "45") (name "Net-(IC2-PD3(INT1{slash}OC2B{slash}PCINT19))") (class "Default")
      (node (ref "11") (pin "MP") (pinfunction "MP_MP") (pintype "passive"))
      (node (ref "IC2") (pin "5") (pinfunction "PD3(INT1/OC2B/PCINT19)_5") (pintype "bidirectional"))
    )
    (net (code "46") (name "Net-(IC2-PD4(T0{slash}XCK{slash}PCINT20))") (class "Default")
      (node (ref "12") (pin "MP") (pinfunction "MP_MP") (pintype "passive"))
      (node (ref "IC2") (pin "6") (pinfunction "PD4(T0/XCK/PCINT20)_6") (pintype "bidirectional"))
    )
    (net (code "47") (name "Net-(IC2-PD5(T1{slash}OC0B{slash}PCINT21))") (class "Default")
      (node (ref "13") (pin "MP") (pinfunction "MP_MP") (pintype "passive"))
      (node (ref "IC2") (pin "11") (pinfunction "PD5(T1/OC0B/PCINT21)_11") (pintype "bidirectional"))
    )
    (net (code "48") (name "Net-(IC2-PD6(AIN0{slash}OC0A{slash}PCINT22))") (class "Default")
      (node (ref "14") (pin "MP") (pinfunction "MP_MP") (pintype "passive"))
      (node (ref "IC2") (pin "12") (pinfunction "PD6(AIN0/OC0A/PCINT22)_12") (pintype "bidirectional"))
    )
    (net (code "49") (name "Net-(IC2-PD7(AIN1{slash}PCINT23))") (class "Default")
      (node (ref "15") (pin "MP") (pinfunction "MP_MP") (pintype "passive"))
      (node (ref "IC2") (pin "13") (pinfunction "PD7(AIN1/PCINT23)_13") (pintype "bidirectional"))
    )
    (net (code "50") (name "Net-(IC3-AGND)") (class "Default")
      (node (ref "D3") (pin "A") (pinfunction "A_A") (pintype "passive"))
      (node (ref "GND10") (pin "MP") (pinfunction "MP_MP") (pintype "passive"))
      (node (ref "GND11") (pin "MP") (pinfunction "MP_MP") (pintype "passive"))
      (node (ref "GND12") (pin "MP") (pinfunction "MP_MP") (pintype "passive"))
      (node (ref "GND15") (pin "MP") (pinfunction "MP_MP") (pintype "passive"))
      (node (ref "GND16") (pin "MP") (pinfunction "MP_MP") (pintype "passive"))
      (node (ref "GND9") (pin "MP") (pinfunction "MP_MP") (pintype "passive"))
      (node (ref "IC3") (pin "22") (pinfunction "AGND_22") (pintype "power_in"))
      (node (ref "IC3") (pin "8") (pinfunction "GND_8") (pintype "power_in"))
      (node (ref "LED3") (pin "K") (pinfunction "C_K") (pintype "passive"))
      (node (ref "LSP10") (pin "MP") (pinfunction "MP_MP") (pintype "passive"))
      (node (ref "LSP11") (pin "MP") (pinfunction "MP_MP") (pintype "passive"))
      (node (ref "LSP12") (pin "MP") (pinfunction "MP_MP") (pintype "passive"))
      (node (ref "R13") (pin "2") (pinfunction "2_2") (pintype "passive"))
      (node (ref "SV5") (pin "1") (pinfunction "1_1") (pintype "passive"))
      (node (ref "SV6") (pin "6") (pinfunction "6_6") (pintype "passive"))
    )
    (net (code "51") (name "Net-(IC3-AVCC)") (class "Default")
      (node (ref "IC3") (pin "20") (pinfunction "AVCC_20") (pintype "passive"))
      (node (ref "IC3") (pin "7") (pinfunction "VCC_7") (pintype "power_in"))
      (node (ref "LSP13") (pin "MP") (pinfunction "MP_MP") (pintype "passive"))
      (node (ref "LSP14") (pin "MP") (pinfunction "MP_MP") (pintype "passive"))
      (node (ref "LSP27") (pin "MP") (pinfunction "MP_MP") (pintype "passive"))
      (node (ref "LSP28") (pin "MP") (pinfunction "MP_MP") (pintype "passive"))
      (node (ref "LSP8") (pin "MP") (pinfunction "MP_MP") (pintype "passive"))
      (node (ref "LSP9") (pin "MP") (pinfunction "MP_MP") (pintype "passive"))
      (node (ref "MOSI4") (pin "MP") (pinfunction "MP_MP") (pintype "passive"))
      (node (ref "Q3") (pin "E") (pinfunction "E_E") (pintype "passive"))
      (node (ref "R11") (pin "2") (pinfunction "2_2") (pintype "passive"))
      (node (ref "SV6") (pin "2") (pinfunction "2_2") (pintype "passive"))
    )
    (net (code "52") (name "Net-(IC3-PB0(ICP1{slash}CLKO{slash}PCINT0))") (class "Default")
      (node (ref "IC3") (pin "14") (pinfunction "PB0(ICP1/CLKO/PCINT0)_14") (pintype "bidirectional"))
      (node (ref "R12") (pin "2") (pinfunction "2_2") (pintype "passive"))
    )
    (net (code "53") (name "Net-(IC3-PB1(OC1A{slash}PCINT1))") (class "Default")
      (node (ref "IC3") (pin "15") (pinfunction "PB1(OC1A/PCINT1)_15") (pintype "bidirectional"))
      (node (ref "SV5") (pin "4") (pinfunction "4_4") (pintype "passive"))
    )
    (net (code "54") (name "Net-(IC3-PB2(SS{slash}OC1B{slash}PCINT2))") (class "Default")
      (node (ref "IC3") (pin "16") (pinfunction "PB2(SS/OC1B/PCINT2)_16") (pintype "bidirectional"))
      (node (ref "SV5") (pin "3") (pinfunction "3_3") (pintype "passive"))
    )
    (net (code "55") (name "Net-(IC3-PB3(MOSI{slash}OC2A{slash}PCINT3))") (class "Default")
      (node (ref "IC3") (pin "17") (pinfunction "PB3(MOSI/OC2A/PCINT3)_17") (pintype "bidirectional"))
      (node (ref "MOSI2") (pin "MP") (pinfunction "MP_MP") (pintype "passive"))
      (node (ref "SV5") (pin "6") (pinfunction "6_6") (pintype "passive"))
      (node (ref "SV6") (pin "4") (pinfunction "4_4") (pintype "passive"))
    )
    (net (code "56") (name "Net-(IC3-PB4(MISO{slash}PCINT4))") (class "Default")
      (node (ref "IC3") (pin "18") (pinfunction "PB4(MISO/PCINT4)_18") (pintype "bidirectional"))
      (node (ref "MISO2") (pin "MP") (pinfunction "MP_MP") (pintype "passive"))
      (node (ref "SV5") (pin "7") (pinfunction "7_7") (pintype "passive"))
      (node (ref "SV6") (pin "1") (pinfunction "1_1") (pintype "passive"))
    )
    (net (code "57") (name "Net-(IC3-PB5(SCK{slash}PCINT5))") (class "Default")
      (node (ref "IC3") (pin "19") (pinfunction "PB5(SCK/PCINT5)_19") (pintype "bidirectional"))
      (node (ref "SCK2") (pin "MP") (pinfunction "MP_MP") (pintype "passive"))
      (node (ref "SV5") (pin "5") (pinfunction "5_5") (pintype "passive"))
      (node (ref "SV6") (pin "3") (pinfunction "3_3") (pintype "passive"))
    )
    (net (code "58") (name "Net-(IC3-PC0(ADC0{slash}PCINT8))") (class "Default")
      (node (ref "IC3") (pin "23") (pinfunction "PC0(ADC0/PCINT8)_23") (pintype "bidirectional"))
      (node (ref "R12") (pin "1") (pinfunction "1_1") (pintype "passive"))
      (node (ref "R13") (pin "1") (pinfunction "1_1") (pintype "passive"))
    )
    (net (code "59") (name "Net-(IC3-PC1(ADC1{slash}PCINT9))") (class "Default")
      (node (ref "IC3") (pin "24") (pinfunction "PC1(ADC1/PCINT9)_24") (pintype "bidirectional"))
      (node (ref "R14") (pin "2") (pinfunction "2_2") (pintype "passive"))
    )
    (net (code "60") (name "Net-(IC3-PC2(ADC2{slash}PCINT10))") (class "Default")
      (node (ref "A9") (pin "MP") (pinfunction "MP_MP") (pintype "passive"))
      (node (ref "IC3") (pin "25") (pinfunction "PC2(ADC2/PCINT10)_25") (pintype "bidirectional"))
    )
    (net (code "61") (name "Net-(IC3-PC3(ADC3{slash}PCINT11))") (class "Default")
      (node (ref "A10") (pin "MP") (pinfunction "MP_MP") (pintype "passive"))
      (node (ref "IC3") (pin "26") (pinfunction "PC3(ADC3/PCINT11)_26") (pintype "bidirectional"))
    )
    (net (code "62") (name "Net-(IC3-PC4(ADC4{slash}SDA{slash}PCINT12))") (class "Default")
      (node (ref "A11") (pin "MP") (pinfunction "MP_MP") (pintype "passive"))
      (node (ref "IC3") (pin "27") (pinfunction "PC4(ADC4/SDA/PCINT12)_27") (pintype "bidirectional"))
    )
    (net (code "63") (name "Net-(IC3-PC5(ADC5{slash}SCLPCINT13))") (class "Default")
      (node (ref "A12") (pin "MP") (pinfunction "MP_MP") (pintype "passive"))
      (node (ref "IC3") (pin "28") (pinfunction "PC5(ADC5/SCLPCINT13)_28") (pintype "bidirectional"))
    )
    (net (code "64") (name "Net-(IC3-PC6({slash}RESET{slash}PCINT14))") (class "Default")
      (node (ref "A15") (pin "MP") (pinfunction "MP_MP") (pintype "passive"))
      (node (ref "A16") (pin "MP") (pinfunction "MP_MP") (pintype "passive"))
      (node (ref "IC3") (pin "1") (pinfunction "PC6(/RESET/PCINT14)_1") (pintype "bidirectional"))
      (node (ref "R11") (pin "1") (pinfunction "1_1") (pintype "passive"))
      (node (ref "SV6") (pin "5") (pinfunction "5_5") (pintype "passive"))
    )
    (net (code "65") (name "Net-(IC3-PD0(RXD{slash}PCINT16))") (class "Default")
      (node (ref "16") (pin "MP") (pinfunction "MP_MP") (pintype "passive"))
      (node (ref "IC3") (pin "2") (pinfunction "PD0(RXD/PCINT16)_2") (pintype "bidirectional"))
    )
    (net (code "66") (name "Net-(IC3-PD1(TXD{slash}PCINT17))") (class "Default")
      (node (ref "17") (pin "MP") (pinfunction "MP_MP") (pintype "passive"))
      (node (ref "IC3") (pin "3") (pinfunction "PD1(TXD/PCINT17)_3") (pintype "bidirectional"))
    )
    (net (code "67") (name "Net-(IC3-PD2(INT0{slash}PCINT18))") (class "Default")
      (node (ref "18") (pin "MP") (pinfunction "MP_MP") (pintype "passive"))
      (node (ref "IC3") (pin "4") (pinfunction "PD2(INT0/PCINT18)_4") (pintype "bidirectional"))
    )
    (net (code "68") (name "Net-(IC3-PD3(INT1{slash}OC2B{slash}PCINT19))") (class "Default")
      (node (ref "19") (pin "MP") (pinfunction "MP_MP") (pintype "passive"))
      (node (ref "IC3") (pin "5") (pinfunction "PD3(INT1/OC2B/PCINT19)_5") (pintype "bidirectional"))
    )
    (net (code "69") (name "Net-(IC3-PD4(T0{slash}XCK{slash}PCINT20))") (class "Default")
      (node (ref "20") (pin "MP") (pinfunction "MP_MP") (pintype "passive"))
      (node (ref "IC3") (pin "6") (pinfunction "PD4(T0/XCK/PCINT20)_6") (pintype "bidirectional"))
    )
    (net (code "70") (name "Net-(IC3-PD5(T1{slash}OC0B{slash}PCINT21))") (class "Default")
      (node (ref "21") (pin "MP") (pinfunction "MP_MP") (pintype "passive"))
      (node (ref "IC3") (pin "11") (pinfunction "PD5(T1/OC0B/PCINT21)_11") (pintype "bidirectional"))
    )
    (net (code "71") (name "Net-(IC3-PD6(AIN0{slash}OC0A{slash}PCINT22))") (class "Default")
      (node (ref "22") (pin "MP") (pinfunction "MP_MP") (pintype "passive"))
      (node (ref "IC3") (pin "12") (pinfunction "PD6(AIN0/OC0A/PCINT22)_12") (pintype "bidirectional"))
    )
    (net (code "72") (name "Net-(IC3-PD7(AIN1{slash}PCINT23))") (class "Default")
      (node (ref "23") (pin "MP") (pinfunction "MP_MP") (pintype "passive"))
      (node (ref "IC3") (pin "13") (pinfunction "PD7(AIN1/PCINT23)_13") (pintype "bidirectional"))
    )
    (net (code "73") (name "Net-(LED1-PadA)") (class "Default")
      (node (ref "LED1") (pin "A") (pinfunction "A_A") (pintype "passive"))
      (node (ref "R7") (pin "1") (pinfunction "1_1") (pintype "passive"))
    )
    (net (code "74") (name "Net-(LED2-PadA)") (class "Default")
      (node (ref "LED2") (pin "A") (pinfunction "A_A") (pintype "passive"))
      (node (ref "R1") (pin "1") (pinfunction "1_1") (pintype "passive"))
    )
    (net (code "75") (name "Net-(LED3-PadA)") (class "Default")
      (node (ref "LED3") (pin "A") (pinfunction "A_A") (pintype "passive"))
      (node (ref "R14") (pin "1") (pinfunction "1_1") (pintype "passive"))
    )
    (net (code "76") (name "Net-(LSP16-PadMP)") (class "Default")
      (node (ref "LSP16") (pin "MP") (pinfunction "MP_MP") (pintype "passive"))
      (node (ref "SV1") (pin "2") (pinfunction "2_2") (pintype "passive"))
    )
    (net (code "77") (name "Net-(LSP17-PadMP)") (class "Default")
      (node (ref "LSP17") (pin "MP") (pinfunction "MP_MP") (pintype "passive"))
      (node (ref "SV2") (pin "2") (pinfunction "2_2") (pintype "passive"))
    )
    (net (code "78") (name "Net-(MOSI3-PadMP)") (class "Default")
      (node (ref "MOSI3") (pin "MP") (pinfunction "MP_MP") (pintype "passive"))
      (node (ref "SV5") (pin "2") (pinfunction "2_2") (pintype "passive"))
    )
    (net (code "79") (name "Net-(Q1-PadC)") (class "Default")
      (node (ref "Q1") (pin "C") (pinfunction "C_C") (pintype "passive"))
      (node (ref "R2") (pin "1") (pinfunction "1_1") (pintype "passive"))
      (node (ref "UB1") (pin "MP") (pinfunction "MP_MP") (pintype "passive"))
      (node (ref "UB2") (pin "MP") (pinfunction "MP_MP") (pintype "passive"))
      (node (ref "UB3") (pin "MP") (pinfunction "MP_MP") (pintype "passive"))
    )
    (net (code "80") (name "Net-(Q2-PadC)") (class "Default")
      (node (ref "Q2") (pin "C") (pinfunction "C_C") (pintype "passive"))
      (node (ref "R10") (pin "1") (pinfunction "1_1") (pintype "passive"))
      (node (ref "UB4") (pin "MP") (pinfunction "MP_MP") (pintype "passive"))
      (node (ref "UB5") (pin "MP") (pinfunction "MP_MP") (pintype "passive"))
      (node (ref "UB6") (pin "MP") (pinfunction "MP_MP") (pintype "passive"))
    )
    (net (code "81") (name "Net-(Q3-PadC)") (class "Default")
      (node (ref "Q3") (pin "C") (pinfunction "C_C") (pintype "passive"))
      (node (ref "R15") (pin "1") (pinfunction "1_1") (pintype "passive"))
      (node (ref "UB7") (pin "MP") (pinfunction "MP_MP") (pintype "passive"))
      (node (ref "UB8") (pin "MP") (pinfunction "MP_MP") (pintype "passive"))
      (node (ref "UB9") (pin "MP") (pinfunction "MP_MP") (pintype "passive"))
    )
    (net (code "82") (name "unconnected-(IC1-AREF-Pad21)") (class "Default")
      (node (ref "IC1") (pin "21") (pinfunction "AREF_21") (pintype "passive"))
    )
    (net (code "83") (name "unconnected-(IC1-PB6(XTAL1{slash}TOSC1{slash}PCINT6)-Pad9)") (class "Default")
      (node (ref "IC1") (pin "9") (pinfunction "PB6(XTAL1/TOSC1/PCINT6)_9") (pintype "bidirectional"))
    )
    (net (code "84") (name "unconnected-(IC1-PB7(XTAL2{slash}TOSC2{slash}PCINT7)-Pad10)") (class "Default")
      (node (ref "IC1") (pin "10") (pinfunction "PB7(XTAL2/TOSC2/PCINT7)_10") (pintype "bidirectional"))
    )
    (net (code "85") (name "unconnected-(IC2-AREF-Pad21)") (class "Default")
      (node (ref "IC2") (pin "21") (pinfunction "AREF_21") (pintype "passive"))
    )
    (net (code "86") (name "unconnected-(IC2-PB6(XTAL1{slash}TOSC1{slash}PCINT6)-Pad9)") (class "Default")
      (node (ref "IC2") (pin "9") (pinfunction "PB6(XTAL1/TOSC1/PCINT6)_9") (pintype "bidirectional"))
    )
    (net (code "87") (name "unconnected-(IC2-PB7(XTAL2{slash}TOSC2{slash}PCINT7)-Pad10)") (class "Default")
      (node (ref "IC2") (pin "10") (pinfunction "PB7(XTAL2/TOSC2/PCINT7)_10") (pintype "bidirectional"))
    )
    (net (code "88") (name "unconnected-(IC3-AREF-Pad21)") (class "Default")
      (node (ref "IC3") (pin "21") (pinfunction "AREF_21") (pintype "passive"))
    )
    (net (code "89") (name "unconnected-(IC3-PB6(XTAL1{slash}TOSC1{slash}PCINT6)-Pad9)") (class "Default")
      (node (ref "IC3") (pin "9") (pinfunction "PB6(XTAL1/TOSC1/PCINT6)_9") (pintype "bidirectional"))
    )
    (net (code "90") (name "unconnected-(IC3-PB7(XTAL2{slash}TOSC2{slash}PCINT7)-Pad10)") (class "Default")
      (node (ref "IC3") (pin "10") (pinfunction "PB7(XTAL2/TOSC2/PCINT7)_10") (pintype "bidirectional"))
    )
    (net (code "91") (name "unconnected-(SV1-Pad8)") (class "Default")
      (node (ref "SV1") (pin "8") (pinfunction "8_8") (pintype "passive"))
    )
    (net (code "92") (name "unconnected-(SV2-Pad8)") (class "Default")
      (node (ref "SV2") (pin "8") (pinfunction "8_8") (pintype "passive"))
    )
    (net (code "93") (name "unconnected-(SV5-Pad8)") (class "Default")
      (node (ref "SV5") (pin "8") (pinfunction "8_8") (pintype "passive"))
    )
  )
)
